# 0_Overview.net
KiCad netlist of a schematic drawn in Altium Designer
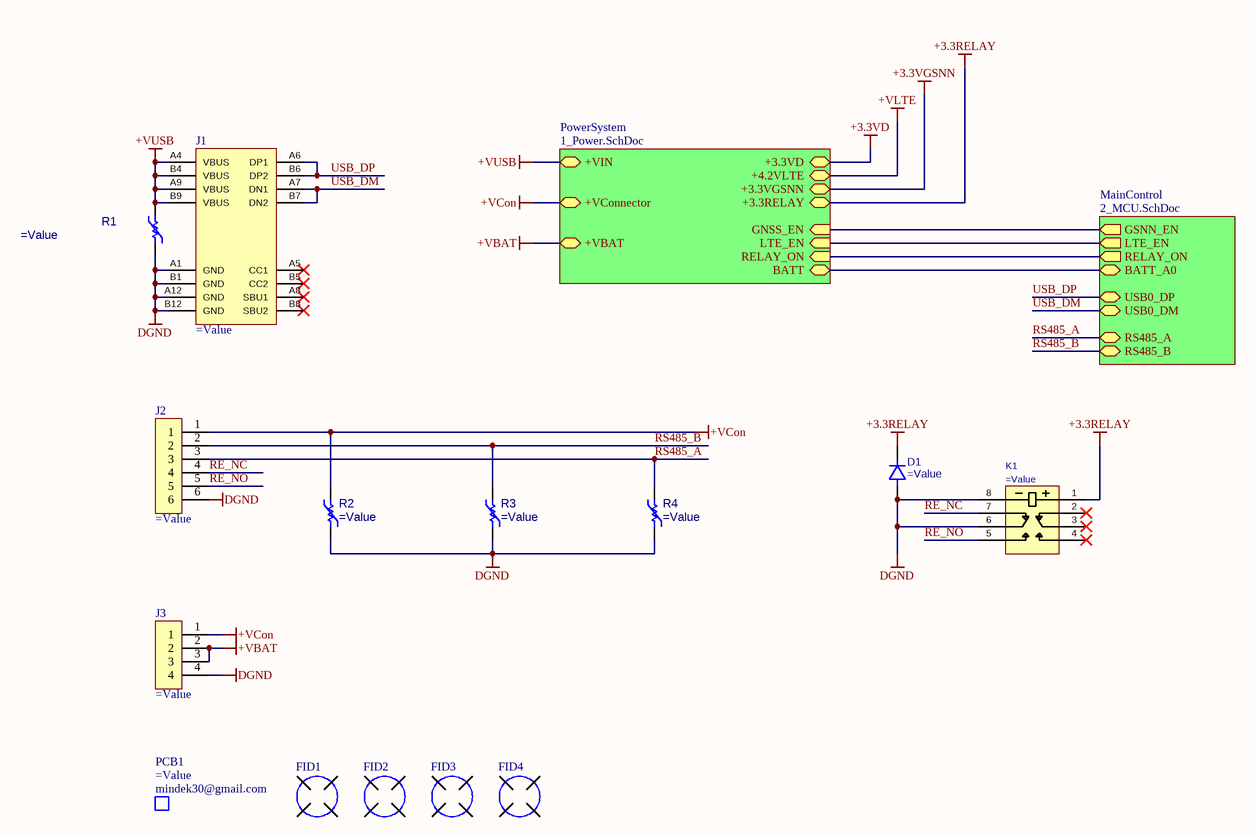
[diagram p0: 0_Overview.SchDoc]

(export (version "E")
  (design (tool "Eeschema 10.0.6"))
  (components
    (comp (ref "D1")
      (value "~")
      (footprint "SOD323")
      (description "DIODE SCHOTTKY 40V 2A 0603")
      (fields (field (name "MANUFACTURER") "Slkor(SLKORMICRO Elec.)") (field (name "PARTNUMBER") "SD103AWS"))
      (libsource (lib "UUSymbol") (part "D_PW_SD103AWS"))
    )
    (comp (ref "FID1")
      (value "FIDUCIAL")
      (footprint "FID")
      (description "Fiducial")
      (fields (field (name "MANUFACTURER") "mindek30@gmail.com") (field (name "PARTNUMBER") "_"))
      (libsource (lib "UUSymbol") (part "FID_FIDUCIAL"))
    )
    (comp (ref "FID2")
      (value "FIDUCIAL")
      (footprint "FID")
      (description "Fiducial")
      (fields (field (name "MANUFACTURER") "mindek30@gmail.com") (field (name "PARTNUMBER") "_"))
      (libsource (lib "UUSymbol") (part "FID_FIDUCIAL"))
    )
    (comp (ref "FID3")
      (value "FIDUCIAL")
      (footprint "FID")
      (description "Fiducial")
      (fields (field (name "MANUFACTURER") "mindek30@gmail.com") (field (name "PARTNUMBER") "_"))
      (libsource (lib "UUSymbol") (part "FID_FIDUCIAL"))
    )
    (comp (ref "FID4")
      (value "FIDUCIAL")
      (footprint "FID")
      (description "Fiducial")
      (fields (field (name "MANUFACTURER") "mindek30@gmail.com") (field (name "PARTNUMBER") "_"))
      (libsource (lib "UUSymbol") (part "FID_FIDUCIAL"))
    )
    (comp (ref "J1")
      (value "~")
      (footprint "GCT_USB4085-GF-A_REVA4")
      (description "CONN RCPT USB2.0 TYPE C 16+8POS")
      (fields (field (name "PARTNUMBER") "USB4085-GF-A") (field (name "MANUFACTURER") "GCT"))
      (libsource (lib "UUSymbol") (part "CON_USBC_USB4085"))
    )
    (comp (ref "J2")
      (value "~")
      (footprint "CON_6P_Header")
      (description "Connector 6 position")
      (libsource (lib "UUSymbol") (part "CON_6P_Heder"))
    )
    (comp (ref "J3")
      (value "~")
      (footprint "CON_4P_Header")
      (description "Connector 4 position")
      (libsource (lib "UUSymbol") (part "CON_4P_Heder"))
    )
    (comp (ref "K1")
      (value "~")
      (footprint "RELAY_HFD4/12-SR")
      (description "Telecom Non Latching 3VDC DPDT SMD Relays RoHS")
      (fields
        (field (name "MANUFACTURER") "Xiamen Hongfa Electroacoustic")
        (field (name "PARTNUMBER") "HFD4/3-S1R")
      )
      (libsource (lib "UUSymbol") (part "SW_RELAY_HFD4/12-SR"))
    )
    (comp (ref "PCB1")
      (value "~")
      (description "BARE PCB")
      (fields (field (name "MANUFACTURER") "mindek30@gmail.com") (field (name "PARTNUMBER") "_"))
      (libsource (lib "UUSymbol") (part "PCB_Bare"))
    )
    (comp (ref "R1")
      (value "~")
      (footprint "R_0603")
      (description "VARISTOR 36V 30A 0603")
      (fields (field (name "MANUFACTURER") "KYOCERA AVX") (field (name "PARTNUMBER") "VCAC060326C820MRP"))
      (libsource (lib "UUSymbol") (part "R_VAR_VCAC060326C820MRP"))
    )
    (comp (ref "R2")
      (value "~")
      (footprint "R_0603")
      (description "VARISTOR 36V 30A 0603")
      (fields (field (name "MANUFACTURER") "KYOCERA AVX") (field (name "PARTNUMBER") "VCAC060326C820MRP"))
      (libsource (lib "UUSymbol") (part "R_VAR_VCAC060326C820MRP"))
    )
    (comp (ref "R3")
      (value "~")
      (footprint "R_0603")
      (description "VARISTOR 36V 30A 0603")
      (fields (field (name "MANUFACTURER") "KYOCERA AVX") (field (name "PARTNUMBER") "VCAC060326C820MRP"))
      (libsource (lib "UUSymbol") (part "R_VAR_VCAC060326C820MRP"))
    )
    (comp (ref "R4")
      (value "~")
      (footprint "R_0603")
      (description "VARISTOR 36V 30A 0603")
      (fields (field (name "MANUFACTURER") "KYOCERA AVX") (field (name "PARTNUMBER") "VCAC060326C820MRP"))
      (libsource (lib "UUSymbol") (part "R_VAR_VCAC060326C820MRP"))
    )
  )
  (nets
    (net (code "1") (name "+3.3RELAY") (class "Default")
      (node (ref "D1") (pin "1") (pinfunction "1_1") (pintype "passive"))
      (node (ref "K1") (pin "1") (pinfunction "1_1") (pintype "passive"))
    )
    (net (code "4") (name "+VBAT") (class "Default")
      (node (ref "J3") (pin "2") (pinfunction "2_2") (pintype "passive"))
      (node (ref "J3") (pin "3") (pinfunction "3_3") (pintype "passive"))
    )
    (net (code "5") (name "+VCon") (class "Default")
      (node (ref "J2") (pin "1") (pinfunction "1_1") (pintype "passive"))
      (node (ref "J3") (pin "1") (pinfunction "1_1") (pintype "passive"))
      (node (ref "R2") (pin "1") (pinfunction "1_1") (pintype "passive"))
    )
    (net (code "7") (name "+VUSB") (class "Default")
      (node (ref "J1") (pin "A4") (pinfunction "VBUS_A4") (pintype "passive"))
      (node (ref "J1") (pin "A9") (pinfunction "VBUS_A9") (pintype "passive"))
      (node (ref "J1") (pin "B4") (pinfunction "VBUS_B4") (pintype "passive"))
      (node (ref "J1") (pin "B9") (pinfunction "VBUS_B9") (pintype "passive"))
      (node (ref "R1") (pin "2") (pinfunction "2_2") (pintype "passive"))
    )
    (net (code "12") (name "/RE_NC") (class "Default")
      (node (ref "J2") (pin "4") (pinfunction "4_4") (pintype "passive"))
      (node (ref "K1") (pin "7") (pinfunction "7_7") (pintype "passive"))
    )
    (net (code "13") (name "/RE_NO") (class "Default")
      (node (ref "J2") (pin "5") (pinfunction "5_5") (pintype "passive"))
      (node (ref "K1") (pin "5") (pinfunction "5_5") (pintype "passive"))
    )
    (net (code "14") (name "/RS485_A") (class "Default")
      (node (ref "J2") (pin "3") (pinfunction "3_3") (pintype "passive"))
      (node (ref "R4") (pin "1") (pinfunction "1_1") (pintype "passive"))
    )
    (net (code "15") (name "/RS485_B") (class "Default")
      (node (ref "J2") (pin "2") (pinfunction "2_2") (pintype "passive"))
      (node (ref "R3") (pin "2") (pinfunction "2_2") (pintype "passive"))
    )
    (net (code "16") (name "/USB_DM") (class "Default")
      (node (ref "J1") (pin "A7") (pinfunction "DN1_A7") (pintype "passive"))
      (node (ref "J1") (pin "B7") (pinfunction "DN2_B7") (pintype "passive"))
    )
    (net (code "17") (name "/USB_DP") (class "Default")
      (node (ref "J1") (pin "A6") (pinfunction "DP1_A6") (pintype "passive"))
      (node (ref "J1") (pin "B6") (pinfunction "DP2_B6") (pintype "passive"))
    )
    (net (code "18") (name "DGND") (class "Default")
      (node (ref "D1") (pin "2") (pinfunction "2_2") (pintype "passive"))
      (node (ref "J1") (pin "A1") (pinfunction "GND_A1") (pintype "passive"))
      (node (ref "J1") (pin "A12") (pinfunction "GND_A12") (pintype "passive"))
      (node (ref "J1") (pin "B1") (pinfunction "GND_B1") (pintype "passive"))
      (node (ref "J1") (pin "B12") (pinfunction "GND_B12") (pintype "passive"))
      (node (ref "J2") (pin "6") (pinfunction "6_6") (pintype "passive"))
      (node (ref "J3") (pin "4") (pinfunction "4_4") (pintype "passive"))
      (node (ref "K1") (pin "6") (pinfunction "6_6") (pintype "passive"))
      (node (ref "K1") (pin "8") (pinfunction "8_8") (pintype "passive"))
      (node (ref "R1") (pin "1") (pinfunction "1_1") (pintype "passive"))
      (node (ref "R2") (pin "2") (pinfunction "2_2") (pintype "passive"))
      (node (ref "R3") (pin "1") (pinfunction "1_1") (pintype "passive"))
      (node (ref "R4") (pin "2") (pinfunction "2_2") (pintype "passive"))
    )
    (net (code "19") (name "unconnected-(J1-CC1-PadA5)") (class "Default")
      (node (ref "J1") (pin "A5") (pinfunction "CC1_A5") (pintype "passive+no_connect"))
    )
    (net (code "20") (name "unconnected-(J1-CC2-PadB5)") (class "Default")
      (node (ref "J1") (pin "B5") (pinfunction "CC2_B5") (pintype "passive+no_connect"))
    )
    (net (code "21") (name "unconnected-(J1-SBU1-PadA8)") (class "Default")
      (node (ref "J1") (pin "A8") (pinfunction "SBU1_A8") (pintype "passive+no_connect"))
    )
    (net (code "22") (name "unconnected-(J1-SBU2-PadB8)") (class "Default")
      (node (ref "J1") (pin "B8") (pinfunction "SBU2_B8") (pintype "passive+no_connect"))
    )
    (net (code "23") (name "unconnected-(K1-Pad2)") (class "Default")
      (node (ref "K1") (pin "2") (pinfunction "2_2") (pintype "passive+no_connect"))
    )
    (net (code "24") (name "unconnected-(K1-Pad3)") (class "Default")
      (node (ref "K1") (pin "3") (pinfunction "3_3") (pintype "passive+no_connect"))
    )
    (net (code "25") (name "unconnected-(K1-Pad4)") (class "Default")
      (node (ref "K1") (pin "4") (pinfunction "4_4") (pintype "passive+no_connect"))
    )
  )
)
